# WaveGenerator.net
KiCad netlist of a schematic drawn in Altium Designer
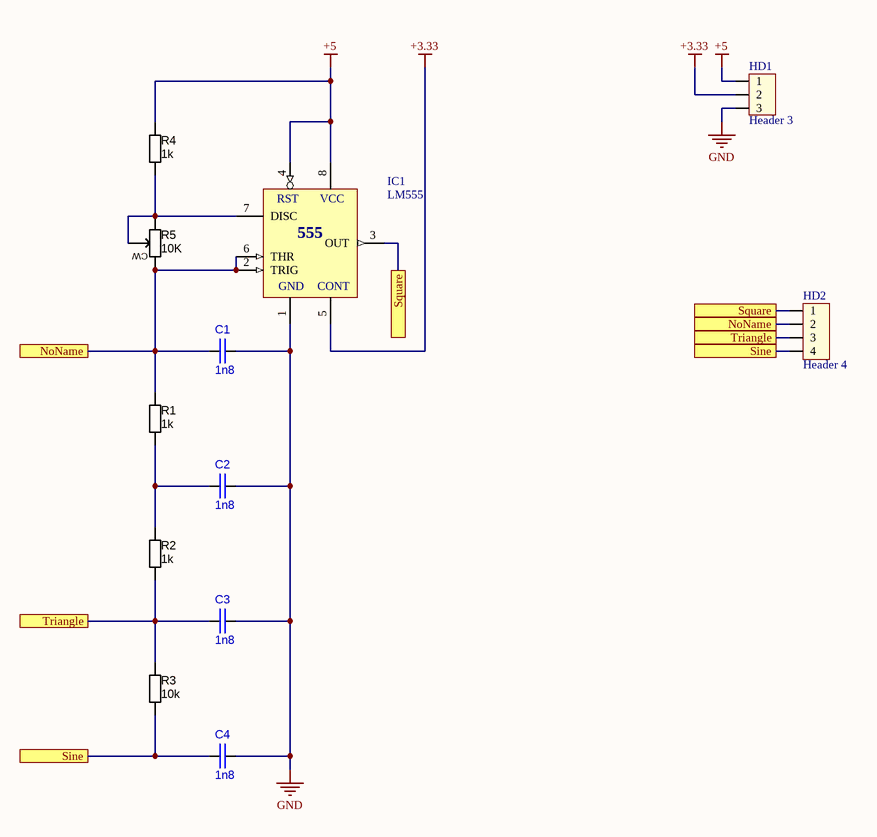
[diagram p0: WaveGenerator.SchDoc]

(export (version "E")
  (design (tool "Eeschema 10.0.6"))
  (components
    (comp (ref "C1")
      (value "1n8")
      (footprint "CAPC2012X135N")
      (description "Capacitor SMD Cer 1.8nF 10% 50V X7R 0805")
      (fields (field (name "TOLERANCE") "±10%") (field (name "Comment") "approved sub OK"))
      (libsource (lib "My library altium") (part "CAP C_0805"))
    )
    (comp (ref "C2")
      (value "1n8")
      (footprint "CAPC2012X135N")
      (description "Capacitor SMD Cer 1.8nF 10% 50V X7R 0805")
      (fields (field (name "TOLERANCE") "±10%") (field (name "Comment") "approved sub OK"))
      (libsource (lib "My library altium") (part "CAP C_0805"))
    )
    (comp (ref "C3")
      (value "1n8")
      (footprint "CAPC2012X135N")
      (description "Capacitor SMD Cer 1.8nF 10% 50V X7R 0805")
      (fields (field (name "TOLERANCE") "±10%") (field (name "Comment") "approved sub OK"))
      (libsource (lib "My library altium") (part "CAP C_0805"))
    )
    (comp (ref "C4")
      (value "1n8")
      (footprint "CAPC2012X135N")
      (description "Capacitor SMD Cer 1.8nF 10% 50V X7R 0805")
      (fields (field (name "TOLERANCE") "±10%") (field (name "Comment") "approved sub OK"))
      (libsource (lib "My library altium") (part "CAP C_0805"))
    )
    (comp (ref "HD1")
      (value "Header 3")
      (footprint "HED3")
      (description "Header 3 (Green)")
      (libsource (lib "My library altium") (part "Header 3"))
    )
    (comp (ref "HD2")
      (value "Header 4")
      (footprint "HED4")
      (description "Header 4 (Green)")
      (libsource (lib "My library altium") (part "Header 4"))
    )
    (comp (ref "IC1")
      (value "LM555")
      (footprint "DIP8/W0.3")
      (description "Timer")
      (libsource (lib "syhaunguyen") (part "LM555"))
    )
    (comp (ref "R1")
      (value "1k")
      (footprint "RESC2012N_ZERO")
      (description "Resistor SMD chip 0.0 Ohm 0.125W 0805")
      (fields (field (name "Comment") "Jumper"))
      (libsource (lib "My library altium") (part "RES_0805"))
    )
    (comp (ref "R2")
      (value "1k")
      (footprint "RESC2012N_ZERO")
      (description "Resistor SMD chip 0.0 Ohm 0.125W 0805")
      (fields (field (name "Comment") "Jumper"))
      (libsource (lib "My library altium") (part "RES_0805"))
    )
    (comp (ref "R3")
      (value "10k")
      (footprint "RESC2012N_ZERO")
      (description "Resistor SMD chip 0.0 Ohm 0.125W 0805")
      (fields (field (name "Comment") "Jumper"))
      (libsource (lib "My library altium") (part "RES_0805"))
    )
    (comp (ref "R4")
      (value "1k")
      (footprint "RESC2012N_ZERO")
      (description "Resistor SMD chip 0.0 Ohm 0.125W 0805")
      (fields (field (name "Comment") "Jumper"))
      (libsource (lib "My library altium") (part "RES_0805"))
    )
    (comp (ref "R5")
      (value "10K")
      (footprint "TRIMPOT_THT_PV36X")
      (description "Trimmer THD 10K 500mW 25-turn")
      (fields (field (name "TOLERANCE") "±10%") (field (name "Comment") "25 turns"))
      (libsource (lib "My library altium") (part "RES_TRIMMER_10K_25T_THT"))
    )
  )
  (nets
    (net (code "1") (name "+3.33") (class "Default")
      (node (ref "HD1") (pin "2") (pinfunction "2_2") (pintype "passive"))
      (node (ref "IC1") (pin "5") (pinfunction "CONT_5") (pintype "passive"))
    )
    (net (code "2") (name "+5") (class "Default")
      (node (ref "HD1") (pin "1") (pinfunction "1_1") (pintype "passive"))
      (node (ref "IC1") (pin "4") (pinfunction "RST_4") (pintype "input"))
      (node (ref "IC1") (pin "8") (pinfunction "VCC_8") (pintype "power_in"))
      (node (ref "R4") (pin "1") (pinfunction "1_1") (pintype "passive"))
    )
    (net (code "3") (name "/NoName") (class "Default")
      (node (ref "C1") (pin "1") (pintype "passive"))
      (node (ref "HD2") (pin "2") (pinfunction "2_2") (pintype "passive"))
      (node (ref "IC1") (pin "2") (pinfunction "TRIG_2") (pintype "input"))
      (node (ref "IC1") (pin "6") (pinfunction "THR_6") (pintype "input"))
      (node (ref "R1") (pin "1") (pinfunction "1_1") (pintype "passive"))
      (node (ref "R5") (pin "CW") (pinfunction "3_CW") (pintype "passive"))
    )
    (net (code "4") (name "/Sine") (class "Default")
      (node (ref "C4") (pin "1") (pintype "passive"))
      (node (ref "HD2") (pin "4") (pinfunction "4_4") (pintype "passive"))
      (node (ref "R3") (pin "2") (pinfunction "2_2") (pintype "passive"))
    )
    (net (code "5") (name "/Square") (class "Default")
      (node (ref "HD2") (pin "1") (pinfunction "1_1") (pintype "passive"))
      (node (ref "IC1") (pin "3") (pinfunction "OUT_3") (pintype "output"))
    )
    (net (code "6") (name "/Triangle") (class "Default")
      (node (ref "C3") (pin "1") (pintype "passive"))
      (node (ref "HD2") (pin "3") (pinfunction "3_3") (pintype "passive"))
      (node (ref "R2") (pin "2") (pinfunction "2_2") (pintype "passive"))
      (node (ref "R3") (pin "1") (pinfunction "1_1") (pintype "passive"))
    )
    (net (code "7") (name "GND") (class "Default")
      (node (ref "C1") (pin "2") (pintype "passive"))
      (node (ref "C2") (pin "2") (pintype "passive"))
      (node (ref "C3") (pin "2") (pintype "passive"))
      (node (ref "C4") (pin "2") (pintype "passive"))
      (node (ref "HD1") (pin "3") (pinfunction "3_3") (pintype "passive"))
      (node (ref "IC1") (pin "1") (pinfunction "GND_1") (pintype "power_in"))
    )
    (net (code "8") (name "Net-(C2-Pad1)") (class "Default")
      (node (ref "C2") (pin "1") (pintype "passive"))
      (node (ref "R1") (pin "2") (pinfunction "2_2") (pintype "passive"))
      (node (ref "R2") (pin "1") (pinfunction "1_1") (pintype "passive"))
    )
    (net (code "9") (name "Net-(IC1-DISC)") (class "Default")
      (node (ref "IC1") (pin "7") (pinfunction "DISC_7") (pintype "open_collector"))
      (node (ref "R4") (pin "2") (pinfunction "2_2") (pintype "passive"))
      (node (ref "R5") (pin "CCW") (pinfunction "1_CCW") (pintype "passive"))
      (node (ref "R5") (pin "W") (pinfunction "2_W") (pintype "passive"))
    )
  )
)
